# FLYTE-v1.net
KiCad netlist of a schematic drawn in EAGLE
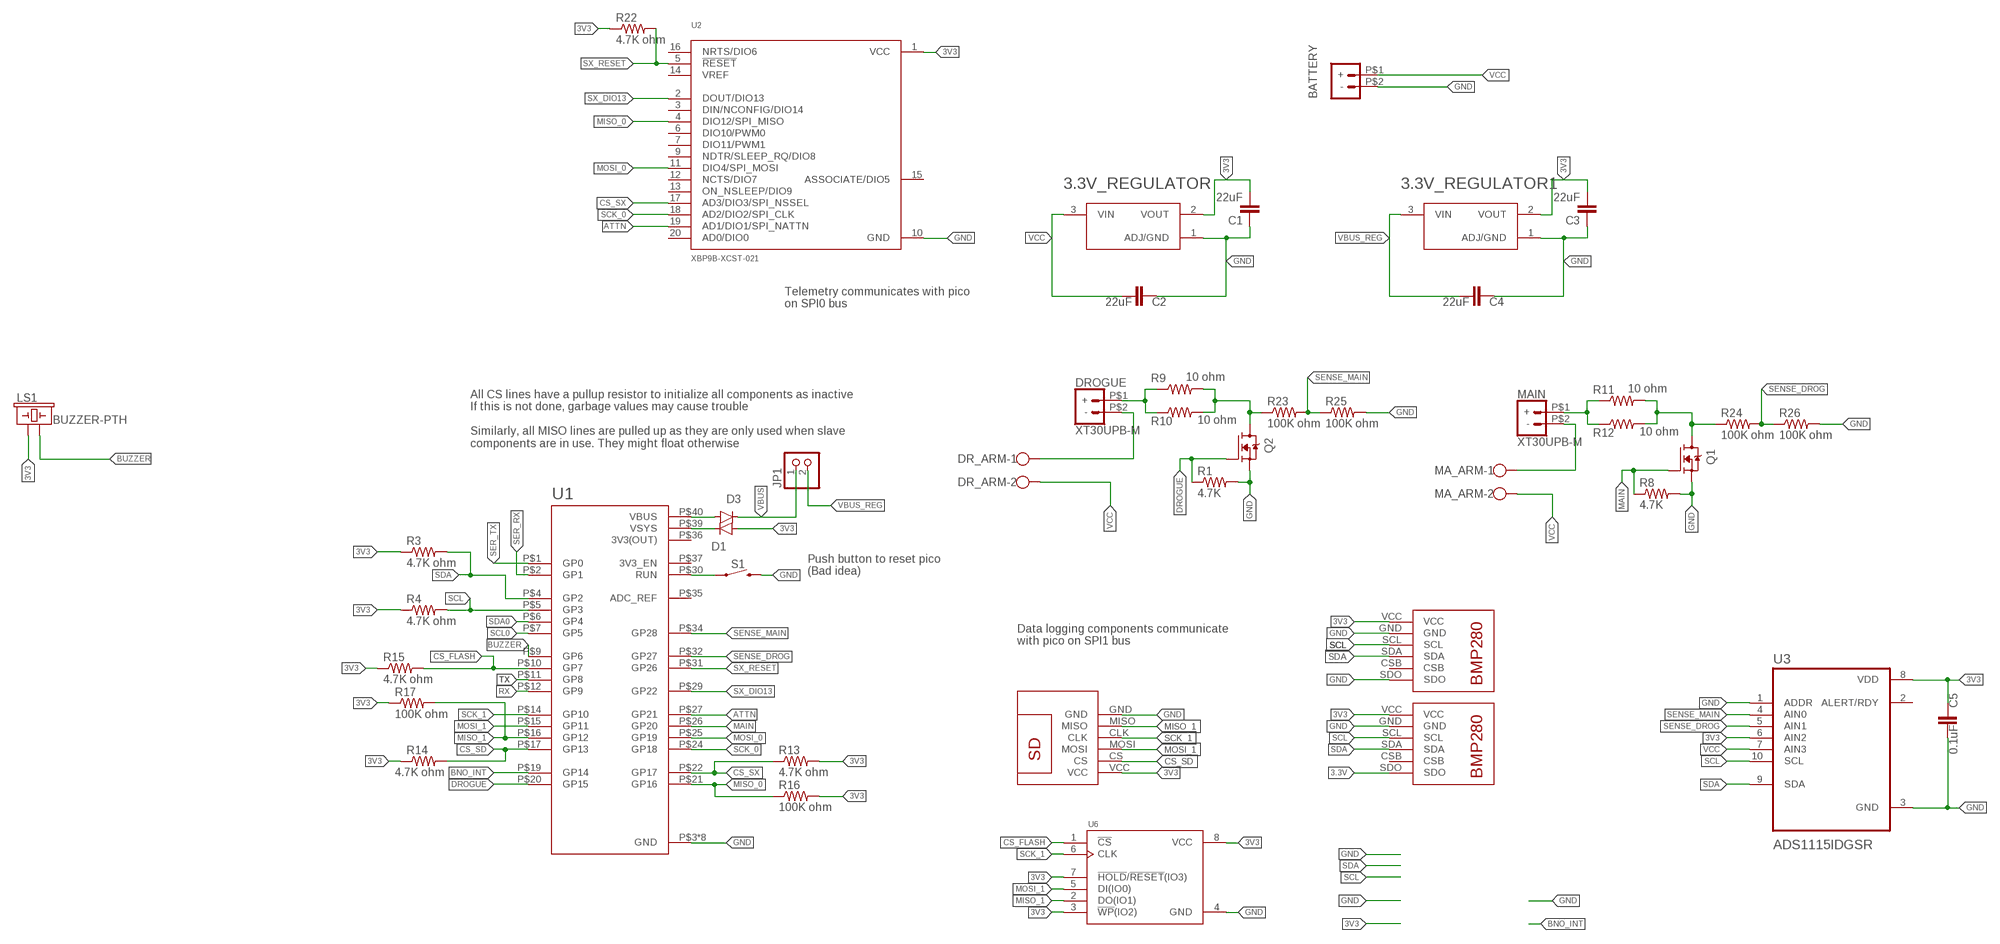
[diagram p0: schematic, sheet 1]

(export (version "E")
  (design (tool "Eeschema 10.0.6"))
  (components
    (comp (ref "3.3V_REGULATOR")
      (value "AMS1117-3.3")
      (footprint "eagle-import:SOT229P700X180-4N")
      (fields (field (name "MF") "Advanced Monolithic Systems"))
      (libsource (lib "eagle-import") (part "AMS1117-3.3"))
    )
    (comp (ref "3.3V_REGULATOR1")
      (value "AMS1117-3.3")
      (footprint "eagle-import:SOT229P700X180-4N")
      (fields (field (name "MF") "Advanced Monolithic Systems"))
      (libsource (lib "eagle-import") (part "AMS1117-3.3"))
    )
    (comp (ref "BATTERY")
      (value "XT30UPB-M")
      (footprint "eagle-import:XT30UPB-M")
      (fields (field (name "MF") "amass"))
      (libsource (lib "eagle-import") (part "XT30UPB-M"))
    )
    (comp (ref "C1")
      (value "22uF")
      (footprint "eagle-import:0805")
      (libsource (lib "eagle-import") (part "22UF-0805-6.3V-20%"))
    )
    (comp (ref "C2")
      (value "22uF")
      (footprint "eagle-import:0805")
      (libsource (lib "eagle-import") (part "22UF-0805-6.3V-20%"))
    )
    (comp (ref "C3")
      (value "22uF")
      (footprint "eagle-import:0805")
      (libsource (lib "eagle-import") (part "22UF-0805-6.3V-20%"))
    )
    (comp (ref "C4")
      (value "22uF")
      (footprint "eagle-import:0805")
      (libsource (lib "eagle-import") (part "22UF-0805-6.3V-20%"))
    )
    (comp (ref "C5")
      (value "0.1uF")
      (footprint "eagle-import:0805")
      (libsource (lib "eagle-import") (part "22UF-0805-6.3V-20%"))
    )
    (comp (ref "D1")
      (value "1N4004")
      (footprint "eagle-import:DO41-10")
      (libsource (lib "eagle-import") (part "1N4004"))
    )
    (comp (ref "D3")
      (value "1N4004")
      (footprint "eagle-import:DO41-10")
      (libsource (lib "eagle-import") (part "1N4004"))
    )
    (comp (ref "DROGUE")
      (value "XT30UPB-M")
      (footprint "eagle-import:XT30UPB-M")
      (fields (field (name "MF") "amass"))
      (libsource (lib "eagle-import") (part "XT30UPB-M"))
    )
    (comp (ref "DR_ARM")
      (value "W237-102")
      (footprint "eagle-import:W237-102")
      (fields (field (name "MPN") "237-102"))
      (libsource (lib "eagle-import") (part "W237-102"))
    )
    (comp (ref "JP1")
      (value "PINHD-1X2")
      (footprint "eagle-import:1X02")
      (libsource (lib "eagle-import") (part "PINHD-1X2"))
    )
    (comp (ref "LS1")
      (value "BUZZER-PTH")
      (footprint "eagle-import:BUZZER-12MM")
      (libsource (lib "eagle-import") (part "BUZZER-PTH"))
    )
    (comp (ref "MAIN")
      (value "XT30UPB-M")
      (footprint "eagle-import:XT30UPB-M")
      (fields (field (name "MF") "amass"))
      (libsource (lib "eagle-import") (part "XT30UPB-M"))
    )
    (comp (ref "MA_ARM")
      (value "W237-102")
      (footprint "eagle-import:W237-102")
      (fields (field (name "MPN") "237-102"))
      (libsource (lib "eagle-import") (part "W237-102"))
    )
    (comp (ref "Q1")
      (value "IRF540NPBF")
      (footprint "eagle-import:TO254P1054X469X1930-3")
      (fields (field (name "MF") "Infineon"))
      (libsource (lib "eagle-import") (part "IRF540NPBF"))
    )
    (comp (ref "Q2")
      (value "IRF540NPBF")
      (footprint "eagle-import:TO254P1054X469X1930-3")
      (fields (field (name "MF") "Infineon"))
      (libsource (lib "eagle-import") (part "IRF540NPBF"))
    )
    (comp (ref "R1")
      (value "4.7K")
      (footprint "eagle-import:R0805")
      (libsource (lib "eagle-import") (part "R-US_R0805"))
    )
    (comp (ref "R3")
      (value "4.7K ohm")
      (footprint "eagle-import:R0805")
      (libsource (lib "eagle-import") (part "R-US_R0805"))
    )
    (comp (ref "R4")
      (value "4.7K ohm")
      (footprint "eagle-import:R0805")
      (libsource (lib "eagle-import") (part "R-US_R0805"))
    )
    (comp (ref "R8")
      (value "4.7K")
      (footprint "eagle-import:R0805")
      (libsource (lib "eagle-import") (part "R-US_R0805"))
    )
    (comp (ref "R9")
      (value "10 ohm")
      (footprint "eagle-import:0207_10")
      (libsource (lib "eagle-import") (part "R-US_0207/10"))
    )
    (comp (ref "R10")
      (value "10 ohm")
      (footprint "eagle-import:0207_10")
      (libsource (lib "eagle-import") (part "R-US_0207/10"))
    )
    (comp (ref "R11")
      (value "10 ohm")
      (footprint "eagle-import:0207_10")
      (libsource (lib "eagle-import") (part "R-US_0207/10"))
    )
    (comp (ref "R12")
      (value "10 ohm")
      (footprint "eagle-import:0207_10")
      (libsource (lib "eagle-import") (part "R-US_0207/10"))
    )
    (comp (ref "R13")
      (value "4.7K ohm")
      (footprint "eagle-import:R0805")
      (libsource (lib "eagle-import") (part "R-US_R0805"))
    )
    (comp (ref "R14")
      (value "4.7K ohm")
      (footprint "eagle-import:R0805")
      (libsource (lib "eagle-import") (part "R-US_R0805"))
    )
    (comp (ref "R15")
      (value "4.7K ohm")
      (footprint "eagle-import:R0805")
      (libsource (lib "eagle-import") (part "R-US_R0805"))
    )
    (comp (ref "R16")
      (value "100K ohm")
      (footprint "eagle-import:R0805")
      (libsource (lib "eagle-import") (part "R-US_R0805"))
    )
    (comp (ref "R17")
      (value "100K ohm")
      (footprint "eagle-import:R0805")
      (libsource (lib "eagle-import") (part "R-US_R0805"))
    )
    (comp (ref "R22")
      (value "4.7K ohm")
      (footprint "eagle-import:R0805")
      (libsource (lib "eagle-import") (part "R-US_R0805"))
    )
    (comp (ref "R23")
      (value "100K ohm")
      (footprint "eagle-import:R0805")
      (libsource (lib "eagle-import") (part "R-US_R0805"))
    )
    (comp (ref "R24")
      (value "100K ohm")
      (footprint "eagle-import:R0805")
      (libsource (lib "eagle-import") (part "R-US_R0805"))
    )
    (comp (ref "R25")
      (value "100K ohm")
      (footprint "eagle-import:R0805")
      (libsource (lib "eagle-import") (part "R-US_R0805"))
    )
    (comp (ref "R26")
      (value "100K ohm")
      (footprint "eagle-import:R0805")
      (libsource (lib "eagle-import") (part "R-US_R0805"))
    )
    (comp (ref "S1")
      (value "MOMENTARY-SWITCH-SPST-PTH-6.0MM")
      (footprint "eagle-import:TACTILE_SWITCH_PTH_6.0MM")
      (libsource (lib "eagle-import") (part "MOMENTARY-SWITCH-SPST-PTH-6.0MM"))
    )
    (comp (ref "U$1")
      (value "BMP280")
      (footprint "eagle-import:BMP280")
      (libsource (lib "eagle-import") (part "BMP280"))
    )
    (comp (ref "U$2")
      (value "BMP280")
      (footprint "eagle-import:BMP280")
      (libsource (lib "eagle-import") (part "BMP280"))
    )
    (comp (ref "U$3")
      (value "SDREADER")
      (footprint "eagle-import:SDREADER")
      (libsource (lib "eagle-import") (part "SDREADER"))
    )
    (comp (ref "U1")
      (value "RASPBERRY_PICO-NO_DEBUG")
      (footprint "eagle-import:PICO-PKG-NO_DEBUG")
      (libsource (lib "eagle-import") (part "RASPBERRY_PICO-NO_DEBUG"))
    )
    (comp (ref "U2")
      (value "XBP9B-XCST-021")
      (footprint "eagle-import:DIP2200W51P200L3294H279Q20P")
      (fields (field (name "MF") "Digi International"))
      (libsource (lib "eagle-import") (part "XBP9B-XCST-021"))
    )
    (comp (ref "U3")
      (value "ADS1115IDGSR")
      (footprint "eagle-import:SOP50P490X110-10N")
      (fields (field (name "MF") "Texas Instruments"))
      (libsource (lib "eagle-import") (part "ADS1115IDGSR"))
    )
    (comp (ref "U6")
      (value "W25Q32JVSSIQ")
      (footprint "eagle-import:SOIC127P790X216-8N")
      (fields (field (name "MF") "Winbond"))
      (libsource (lib "eagle-import") (part "W25Q32JVSSIQ"))
    )
  )
  (nets
    (net (code "1") (name "/3V3(OUT)") (class "Default")
      (node (ref "U1") (pin "P$36") (pinfunction "3V3(OUT)_P$36") (pintype "power_in"))
    )
    (net (code "2") (name "3.3V") (class "Default")
      (node (ref "U$2") (pin "SDO") (pinfunction "SDO_SDO") (pintype "bidirectional"))
    )
    (net (code "3") (name "3V3") (class "Default")
      (node (ref "3.3V_REGULATOR") (pin "2") (pinfunction "VOUT_2") (pintype "output"))
      (node (ref "3.3V_REGULATOR1") (pin "2") (pinfunction "VOUT_2") (pintype "output"))
      (node (ref "C1") (pin "2") (pinfunction "2_2") (pintype "passive"))
      (node (ref "C3") (pin "2") (pinfunction "2_2") (pintype "passive"))
      (node (ref "C5") (pin "1") (pinfunction "1_1") (pintype "passive"))
      (node (ref "D1") (pin "A") (pinfunction "A_A") (pintype "passive"))
      (node (ref "LS1") (pin "+") (pinfunction "1_+") (pintype "passive"))
      (node (ref "R13") (pin "2") (pinfunction "2_2") (pintype "passive"))
      (node (ref "R14") (pin "1") (pinfunction "1_1") (pintype "passive"))
      (node (ref "R15") (pin "1") (pinfunction "1_1") (pintype "passive"))
      (node (ref "R16") (pin "2") (pinfunction "2_2") (pintype "passive"))
      (node (ref "R17") (pin "1") (pinfunction "1_1") (pintype "passive"))
      (node (ref "R22") (pin "1") (pinfunction "1_1") (pintype "passive"))
      (node (ref "R3") (pin "1") (pinfunction "1_1") (pintype "passive"))
      (node (ref "R4") (pin "1") (pinfunction "1_1") (pintype "passive"))
      (node (ref "U$1") (pin "VCC") (pinfunction "VCC_VCC") (pintype "bidirectional"))
      (node (ref "U$2") (pin "VCC") (pinfunction "VCC_VCC") (pintype "bidirectional"))
      (node (ref "U$3") (pin "VCC") (pinfunction "VCC_VCC") (pintype "bidirectional"))
      (node (ref "U2") (pin "1") (pinfunction "VCC_1") (pintype "power_in"))
      (node (ref "U3") (pin "6") (pinfunction "AIN2_6") (pintype "input"))
      (node (ref "U3") (pin "8") (pinfunction "VDD_8") (pintype "power_in"))
      (node (ref "U6") (pin "3") (pinfunction "~{WP}(IO2)_3") (pintype "bidirectional"))
      (node (ref "U6") (pin "7") (pinfunction "~{HOLD}/~{RESET}(IO3)_7") (pintype "bidirectional"))
      (node (ref "U6") (pin "8") (pinfunction "VCC_8") (pintype "power_in"))
    )
    (net (code "4") (name "ATTN") (class "Default")
      (node (ref "U1") (pin "P$27") (pinfunction "GP21_P$27") (pintype "bidirectional"))
      (node (ref "U2") (pin "19") (pinfunction "AD1/DIO1/SPI_NATTN_19") (pintype "bidirectional"))
    )
    (net (code "5") (name "BNO_INT") (class "Default")
      (node (ref "U1") (pin "P$19") (pinfunction "GP14_P$19") (pintype "bidirectional"))
    )
    (net (code "6") (name "BUZZER") (class "Default")
      (node (ref "LS1") (pin "-") (pinfunction "2_-") (pintype "passive"))
      (node (ref "U1") (pin "P$9") (pinfunction "GP6_P$9") (pintype "bidirectional"))
    )
    (net (code "7") (name "CS_FLASH") (class "Default")
      (node (ref "R15") (pin "2") (pinfunction "2_2") (pintype "passive"))
      (node (ref "U1") (pin "P$10") (pinfunction "GP7_P$10") (pintype "bidirectional"))
      (node (ref "U6") (pin "1") (pinfunction "~{CS}_1") (pintype "input"))
    )
    (net (code "8") (name "CS_SD") (class "Default")
      (node (ref "R14") (pin "2") (pinfunction "2_2") (pintype "passive"))
      (node (ref "U$3") (pin "CS") (pinfunction "CS_CS") (pintype "bidirectional"))
      (node (ref "U1") (pin "P$17") (pinfunction "GP13_P$17") (pintype "bidirectional"))
    )
    (net (code "9") (name "CS_SX") (class "Default")
      (node (ref "R13") (pin "1") (pinfunction "1_1") (pintype "passive"))
      (node (ref "U1") (pin "P$22") (pinfunction "GP17_P$22") (pintype "bidirectional"))
      (node (ref "U2") (pin "17") (pinfunction "AD3/DIO3/SPI_NSSEL_17") (pintype "bidirectional"))
    )
    (net (code "10") (name "DROGUE") (class "Default")
      (node (ref "Q2") (pin "1") (pinfunction "G_1") (pintype "passive"))
      (node (ref "R1") (pin "1") (pinfunction "1_1") (pintype "passive"))
      (node (ref "U1") (pin "P$20") (pinfunction "GP15_P$20") (pintype "bidirectional"))
    )
    (net (code "11") (name "GND") (class "Default")
      (node (ref "3.3V_REGULATOR") (pin "1") (pinfunction "ADJ/GND_1") (pintype "power_in"))
      (node (ref "3.3V_REGULATOR1") (pin "1") (pinfunction "ADJ/GND_1") (pintype "power_in"))
      (node (ref "BATTERY") (pin "P$2") (pinfunction "-_P$2") (pintype "passive"))
      (node (ref "C1") (pin "1") (pinfunction "1_1") (pintype "passive"))
      (node (ref "C2") (pin "1") (pinfunction "1_1") (pintype "passive"))
      (node (ref "C3") (pin "1") (pinfunction "1_1") (pintype "passive"))
      (node (ref "C4") (pin "1") (pinfunction "1_1") (pintype "passive"))
      (node (ref "C5") (pin "2") (pinfunction "2_2") (pintype "passive"))
      (node (ref "Q1") (pin "3") (pinfunction "S_3") (pintype "passive"))
      (node (ref "Q2") (pin "3") (pinfunction "S_3") (pintype "passive"))
      (node (ref "R1") (pin "2") (pinfunction "2_2") (pintype "passive"))
      (node (ref "R25") (pin "2") (pinfunction "2_2") (pintype "passive"))
      (node (ref "R26") (pin "2") (pinfunction "2_2") (pintype "passive"))
      (node (ref "R8") (pin "2") (pinfunction "2_2") (pintype "passive"))
      (node (ref "S1") (pin "3") (pinfunction "2_3") (pintype "passive"))
      (node (ref "U$1") (pin "GND") (pinfunction "GND_GND") (pintype "bidirectional"))
      (node (ref "U$1") (pin "SDO") (pinfunction "SDO_SDO") (pintype "bidirectional"))
      (node (ref "U$2") (pin "GND") (pinfunction "GND_GND") (pintype "bidirectional"))
      (node (ref "U$3") (pin "GND") (pinfunction "GND_GND") (pintype "bidirectional"))
      (node (ref "U1") (pin "P$13") (pinfunction "GND_P$13") (pintype "power_in"))
      (node (ref "U1") (pin "P$18") (pinfunction "GND_P$18") (pintype "power_in"))
      (node (ref "U1") (pin "P$23") (pinfunction "GND_P$23") (pintype "power_in"))
      (node (ref "U1") (pin "P$28") (pinfunction "GND_P$28") (pintype "power_in"))
      (node (ref "U1") (pin "P$3") (pinfunction "GND_P$3") (pintype "power_in"))
      (node (ref "U1") (pin "P$33") (pinfunction "GND_P$33") (pintype "power_in"))
      (node (ref "U1") (pin "P$38") (pinfunction "GND_P$38") (pintype "power_in"))
      (node (ref "U1") (pin "P$8") (pinfunction "GND_P$8") (pintype "power_in"))
      (node (ref "U2") (pin "10") (pinfunction "GND_10") (pintype "power_in"))
      (node (ref "U3") (pin "1") (pinfunction "ADDR_1") (pintype "input"))
      (node (ref "U3") (pin "3") (pinfunction "GND_3") (pintype "power_in"))
      (node (ref "U6") (pin "4") (pinfunction "GND_4") (pintype "power_in"))
    )
    (net (code "12") (name "MAIN") (class "Default")
      (node (ref "Q1") (pin "1") (pinfunction "G_1") (pintype "passive"))
      (node (ref "R8") (pin "1") (pinfunction "1_1") (pintype "passive"))
      (node (ref "U1") (pin "P$26") (pinfunction "GP20_P$26") (pintype "bidirectional"))
    )
    (net (code "13") (name "MISO_0") (class "Default")
      (node (ref "R16") (pin "1") (pinfunction "1_1") (pintype "passive"))
      (node (ref "U1") (pin "P$21") (pinfunction "GP16_P$21") (pintype "bidirectional"))
      (node (ref "U2") (pin "4") (pinfunction "DIO12/SPI_MISO_4") (pintype "bidirectional"))
    )
    (net (code "14") (name "MISO_1") (class "Default")
      (node (ref "R17") (pin "2") (pinfunction "2_2") (pintype "passive"))
      (node (ref "U$3") (pin "MISO") (pinfunction "MISO_MISO") (pintype "bidirectional"))
      (node (ref "U1") (pin "P$16") (pinfunction "GP12_P$16") (pintype "bidirectional"))
      (node (ref "U6") (pin "2") (pinfunction "DO(IO1)_2") (pintype "bidirectional"))
    )
    (net (code "15") (name "MOSI_0") (class "Default")
      (node (ref "U1") (pin "P$25") (pinfunction "GP19_P$25") (pintype "bidirectional"))
      (node (ref "U2") (pin "11") (pinfunction "DIO4/SPI_MOSI_11") (pintype "bidirectional"))
    )
    (net (code "16") (name "MOSI_1") (class "Default")
      (node (ref "U$3") (pin "MOSI") (pinfunction "MOSI_MOSI") (pintype "bidirectional"))
      (node (ref "U1") (pin "P$15") (pinfunction "GP11_P$15") (pintype "bidirectional"))
      (node (ref "U6") (pin "5") (pinfunction "DI(IO0)_5") (pintype "bidirectional"))
    )
    (net (code "17") (name "Net-(DROGUE-+)") (class "Default")
      (node (ref "DROGUE") (pin "P$1") (pinfunction "+_P$1") (pintype "passive"))
      (node (ref "R10") (pin "1") (pinfunction "1_1") (pintype "passive"))
      (node (ref "R9") (pin "1") (pinfunction "1_1") (pintype "passive"))
    )
    (net (code "18") (name "Net-(DROGUE--)") (class "Default")
      (node (ref "DROGUE") (pin "P$2") (pinfunction "-_P$2") (pintype "passive"))
      (node (ref "DR_ARM") (pin "1") (pinfunction "KL_1") (pintype "passive"))
    )
    (net (code "19") (name "Net-(MAIN-+)") (class "Default")
      (node (ref "MAIN") (pin "P$1") (pinfunction "+_P$1") (pintype "passive"))
      (node (ref "R11") (pin "1") (pinfunction "1_1") (pintype "passive"))
      (node (ref "R12") (pin "1") (pinfunction "1_1") (pintype "passive"))
    )
    (net (code "20") (name "Net-(MAIN--)") (class "Default")
      (node (ref "MAIN") (pin "P$2") (pinfunction "-_P$2") (pintype "passive"))
      (node (ref "MA_ARM") (pin "1") (pinfunction "KL_1") (pintype "passive"))
    )
    (net (code "21") (name "Net-(Q1-D)") (class "Default")
      (node (ref "Q1") (pin "2") (pinfunction "D_2") (pintype "passive"))
      (node (ref "R11") (pin "2") (pinfunction "2_2") (pintype "passive"))
      (node (ref "R12") (pin "2") (pinfunction "2_2") (pintype "passive"))
      (node (ref "R24") (pin "1") (pinfunction "1_1") (pintype "passive"))
    )
    (net (code "22") (name "Net-(Q2-D)") (class "Default")
      (node (ref "Q2") (pin "2") (pinfunction "D_2") (pintype "passive"))
      (node (ref "R10") (pin "2") (pinfunction "2_2") (pintype "passive"))
      (node (ref "R23") (pin "1") (pinfunction "1_1") (pintype "passive"))
      (node (ref "R9") (pin "2") (pinfunction "2_2") (pintype "passive"))
    )
    (net (code "23") (name "Net-(U1-RUN)") (class "Default")
      (node (ref "S1") (pin "1") (pinfunction "1_1") (pintype "passive"))
      (node (ref "U1") (pin "P$30") (pinfunction "RUN_P$30") (pintype "input"))
    )
    (net (code "24") (name "Net-(U1-VBUS)") (class "Default")
      (node (ref "D3") (pin "A") (pinfunction "A_A") (pintype "passive"))
      (node (ref "U1") (pin "P$40") (pinfunction "VBUS_P$40") (pintype "power_in"))
    )
    (net (code "25") (name "Net-(U1-VSYS)") (class "Default")
      (node (ref "D1") (pin "C") (pinfunction "C_C") (pintype "passive"))
      (node (ref "U1") (pin "P$39") (pinfunction "VSYS_P$39") (pintype "power_in"))
    )
    (net (code "26") (name "RX") (class "Default")
      (node (ref "U1") (pin "P$12") (pinfunction "GP9_P$12") (pintype "bidirectional"))
    )
    (net (code "27") (name "SCK_0") (class "Default")
      (node (ref "U1") (pin "P$24") (pinfunction "GP18_P$24") (pintype "bidirectional"))
      (node (ref "U2") (pin "18") (pinfunction "AD2/DIO2/SPI_CLK_18") (pintype "bidirectional"))
    )
    (net (code "28") (name "SCK_1") (class "Default")
      (node (ref "U$3") (pin "CLK") (pinfunction "CLK_CLK") (pintype "bidirectional"))
      (node (ref "U1") (pin "P$14") (pinfunction "GP10_P$14") (pintype "bidirectional"))
      (node (ref "U6") (pin "6") (pinfunction "CLK_6") (pintype "input"))
    )
    (net (code "29") (name "SCL") (class "Default")
      (node (ref "R4") (pin "2") (pinfunction "2_2") (pintype "passive"))
      (node (ref "U$1") (pin "SCL") (pinfunction "SCL_SCL") (pintype "bidirectional"))
      (node (ref "U$2") (pin "SCL") (pinfunction "SCL_SCL") (pintype "bidirectional"))
      (node (ref "U1") (pin "P$5") (pinfunction "GP3_P$5") (pintype "bidirectional"))
      (node (ref "U3") (pin "10") (pinfunction "SCL_10") (pintype "input"))
    )
    (net (code "30") (name "SCL0") (class "Default")
      (node (ref "U1") (pin "P$7") (pinfunction "GP5_P$7") (pintype "bidirectional"))
    )
    (net (code "31") (name "SDA") (class "Default")
      (node (ref "R3") (pin "2") (pinfunction "2_2") (pintype "passive"))
      (node (ref "U$1") (pin "SDA") (pinfunction "SDA_SDA") (pintype "bidirectional"))
      (node (ref "U$2") (pin "SDA") (pinfunction "SDA_SDA") (pintype "bidirectional"))
      (node (ref "U1") (pin "P$4") (pinfunction "GP2_P$4") (pintype "bidirectional"))
      (node (ref "U3") (pin "9") (pinfunction "SDA_9") (pintype "bidirectional"))
    )
    (net (code "32") (name "SDA0") (class "Default")
      (node (ref "U1") (pin "P$6") (pinfunction "GP4_P$6") (pintype "bidirectional"))
    )
    (net (code "33") (name "SENSE_DROG") (class "Default")
      (node (ref "R24") (pin "2") (pinfunction "2_2") (pintype "passive"))
      (node (ref "R26") (pin "1") (pinfunction "1_1") (pintype "passive"))
      (node (ref "U1") (pin "P$32") (pinfunction "GP27_P$32") (pintype "bidirectional"))
      (node (ref "U3") (pin "5") (pinfunction "AIN1_5") (pintype "input"))
    )
    (net (code "34") (name "SENSE_MAIN") (class "Default")
      (node (ref "R23") (pin "2") (pinfunction "2_2") (pintype "passive"))
      (node (ref "R25") (pin "1") (pinfunction "1_1") (pintype "passive"))
      (node (ref "U1") (pin "P$34") (pinfunction "GP28_P$34") (pintype "bidirectional"))
      (node (ref "U3") (pin "4") (pinfunction "AIN0_4") (pintype "input"))
    )
    (net (code "35") (name "SER_RX") (class "Default")
      (node (ref "U1") (pin "P$2") (pinfunction "GP1_P$2") (pintype "bidirectional"))
    )
    (net (code "36") (name "SER_TX") (class "Default")
      (node (ref "U1") (pin "P$1") (pinfunction "GP0_P$1") (pintype "bidirectional"))
    )
    (net (code "37") (name "SX_DIO13") (class "Default")
      (node (ref "U1") (pin "P$29") (pinfunction "GP22_P$29") (pintype "bidirectional"))
      (node (ref "U2") (pin "2") (pinfunction "DOUT/DIO13_2") (pintype "bidirectional"))
    )
    (net (code "38") (name "SX_RESET") (class "Default")
      (node (ref "R22") (pin "2") (pinfunction "2_2") (pintype "passive"))
      (node (ref "U1") (pin "P$31") (pinfunction "GP26_P$31") (pintype "bidirectional"))
      (node (ref "U2") (pin "5") (pinfunction "~{RESET}_5") (pintype "input"))
    )
    (net (code "39") (name "TX") (class "Default")
      (node (ref "U1") (pin "P$11") (pinfunction "GP8_P$11") (pintype "bidirectional"))
    )
    (net (code "40") (name "VBUS") (class "Default")
      (node (ref "D3") (pin "C") (pinfunction "C_C") (pintype "passive"))
      (node (ref "JP1") (pin "1") (pinfunction "1_1") (pintype "passive"))
    )
    (net (code "41") (name "VBUS_REG") (class "Default")
      (node (ref "3.3V_REGULATOR1") (pin "3") (pinfunction "VIN_3") (pintype "input"))
      (node (ref "C4") (pin "2") (pinfunction "2_2") (pintype "passive"))
      (node (ref "JP1") (pin "2") (pinfunction "2_2") (pintype "passive"))
    )
    (net (code "42") (name "VCC") (class "Default")
      (node (ref "3.3V_REGULATOR") (pin "3") (pinfunction "VIN_3") (pintype "input"))
      (node (ref "BATTERY") (pin "P$1") (pinfunction "+_P$1") (pintype "passive"))
      (node (ref "C2") (pin "2") (pinfunction "2_2") (pintype "passive"))
      (node (ref "DR_ARM") (pin "2") (pinfunction "KL_2") (pintype "passive"))
      (node (ref "MA_ARM") (pin "2") (pinfunction "KL_2") (pintype "passive"))
      (node (ref "U3") (pin "7") (pinfunction "AIN3_7") (pintype "input"))
    )
    (net (code "43") (name "unconnected-(U$1-PadCSB)") (class "Default")
      (node (ref "U$1") (pin "CSB") (pinfunction "CSB_CSB") (pintype "bidirectional"))
    )
    (net (code "44") (name "unconnected-(U$2-PadCSB)") (class "Default")
      (node (ref "U$2") (pin "CSB") (pinfunction "CSB_CSB") (pintype "bidirectional"))
    )
    (net (code "45") (name "unconnected-(U1-3V3_EN-PadP$37)") (class "Default")
      (node (ref "U1") (pin "P$37") (pinfunction "3V3_EN_P$37") (pintype "input"))
    )
    (net (code "46") (name "unconnected-(U1-ADC_REF-PadP$35)") (class "Default")
      (node (ref "U1") (pin "P$35") (pinfunction "ADC_REF_P$35") (pintype "input"))
    )
    (net (code "47") (name "unconnected-(U2-AD0{slash}DIO0-Pad20)") (class "Default")
      (node (ref "U2") (pin "20") (pinfunction "AD0/DIO0_20") (pintype "bidirectional"))
    )
    (net (code "48") (name "unconnected-(U2-ASSOCIATE{slash}DIO5-Pad15)") (class "Default")
      (node (ref "U2") (pin "15") (pinfunction "ASSOCIATE/DIO5_15") (pintype "output"))
    )
    (net (code "49") (name "unconnected-(U2-DIN{slash}NCONFIG{slash}DIO14-Pad3)") (class "Default")
      (node (ref "U2") (pin "3") (pinfunction "DIN/NCONFIG/DIO14_3") (pintype "bidirectional"))
    )
    (net (code "50") (name "unconnected-(U2-DIO10{slash}PWM0-Pad6)") (class "Default")
      (node (ref "U2") (pin "6") (pinfunction "DIO10/PWM0_6") (pintype "bidirectional"))
    )
    (net (code "51") (name "unconnected-(U2-DIO11{slash}PWM1-Pad7)") (class "Default")
      (node (ref "U2") (pin "7") (pinfunction "DIO11/PWM1_7") (pintype "bidirectional"))
    )
    (net (code "52") (name "unconnected-(U2-NCTS{slash}DIO7-Pad12)") (class "Default")
      (node (ref "U2") (pin "12") (pinfunction "NCTS/DIO7_12") (pintype "bidirectional"))
    )
    (net (code "53") (name "unconnected-(U2-NDTR{slash}SLEEP_RQ{slash}DIO8-Pad9)") (class "Default")
      (node (ref "U2") (pin "9") (pinfunction "NDTR/SLEEP_RQ/DIO8_9") (pintype "bidirectional"))
    )
    (net (code "54") (name "unconnected-(U2-NRTS{slash}DIO6-Pad16)") (class "Default")
      (node (ref "U2") (pin "16") (pinfunction "NRTS/DIO6_16") (pintype "input"))
    )
    (net (code "55") (name "unconnected-(U2-ON_NSLEEP{slash}DIO9-Pad13)") (class "Default")
      (node (ref "U2") (pin "13") (pinfunction "ON_NSLEEP/DIO9_13") (pintype "bidirectional"))
    )
    (net (code "56") (name "unconnected-(U2-VREF-Pad14)") (class "Default")
      (node (ref "U2") (pin "14") (pinfunction "VREF_14") (pintype "input"))
    )
    (net (code "57") (name "unconnected-(U3-ALERT{slash}RDY-Pad2)") (class "Default")
      (node (ref "U3") (pin "2") (pinfunction "ALERT/RDY_2") (pintype "output"))
    )
  )
)
